# pca10056_sheet3_pin_map.net
KiCad netlist of a schematic drawn in Altium Designer
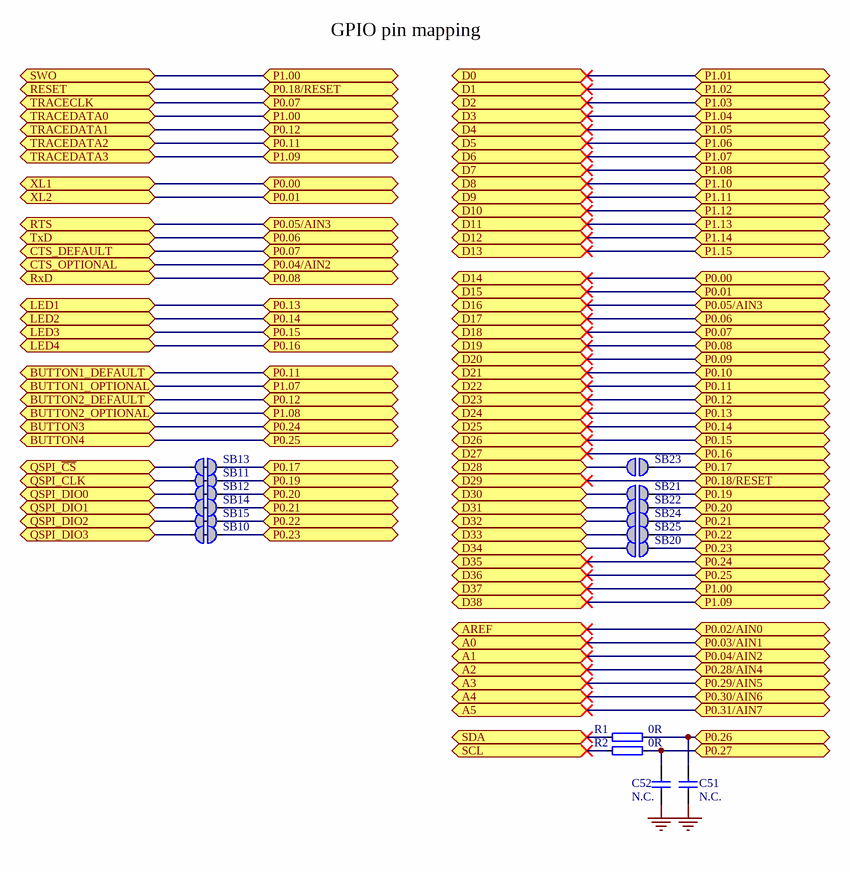
[diagram p0: pca10056_sheet3_pin_map.SchDoc]

(export (version "E")
  (design (tool "Eeschema 10.0.6"))
  (components
    (comp (ref "C51")
      (value "N.C.")
      (footprint "CAPC0603X03L_C")
      (description "Not mounted")
      (fields (field (name "PART NUMBER") "C0201-N.C.") (field (name "PUBLISHER") "Nordic Semiconductor"))
      (libsource (lib "Nordic Passive DB") (part "CAP"))
    )
    (comp (ref "C52")
      (value "N.C.")
      (footprint "CAPC0603X03L_C")
      (description "Not mounted")
      (fields (field (name "PART NUMBER") "C0201-N.C.") (field (name "PUBLISHER") "Nordic Semiconductor"))
      (libsource (lib "Nordic Passive DB") (part "CAP"))
    )
    (comp (ref "R1")
      (value "0R")
      (footprint "RESC0603X03L_C")
      (description "Resistor, ±5%, 0.05W")
      (fields (field (name "PART NUMBER") "R0201-0R") (field (name "PUBLISHER") "Nordic Semiconductor"))
      (libsource (lib "Nordic Passive DB") (part "RES_1"))
    )
    (comp (ref "R2")
      (value "0R")
      (footprint "RESC0603X03L_C")
      (description "Resistor, ±5%, 0.05W")
      (fields (field (name "PART NUMBER") "R0201-0R") (field (name "PUBLISHER") "Nordic Semiconductor"))
      (libsource (lib "Nordic Passive DB") (part "RES_1"))
    )
    (comp (ref "SB10")
      (value "Solderbridge")
      (footprint "Solderbridge_Shorted")
      (description "Shorted Solderbridge")
      (fields
        (field (name "PART NUMBER") "Solderbridge Shorted")
        (field (name "PUBLISHER") "Nordic Semiconductor")
      )
      (libsource (lib "Nordic Passive DB") (part "SOLDERBRIDGE_SHORTED"))
    )
    (comp (ref "SB11")
      (value "Solderbridge")
      (footprint "Solderbridge_Shorted")
      (description "Shorted Solderbridge")
      (fields
        (field (name "PART NUMBER") "Solderbridge Shorted")
        (field (name "PUBLISHER") "Nordic Semiconductor")
      )
      (libsource (lib "Nordic Passive DB") (part "SOLDERBRIDGE_SHORTED"))
    )
    (comp (ref "SB12")
      (value "Solderbridge")
      (footprint "Solderbridge_Shorted")
      (description "Shorted Solderbridge")
      (fields
        (field (name "PART NUMBER") "Solderbridge Shorted")
        (field (name "PUBLISHER") "Nordic Semiconductor")
      )
      (libsource (lib "Nordic Passive DB") (part "SOLDERBRIDGE_SHORTED"))
    )
    (comp (ref "SB13")
      (value "Solderbridge")
      (footprint "Solderbridge_Shorted")
      (description "Shorted Solderbridge")
      (fields
        (field (name "PART NUMBER") "Solderbridge Shorted")
        (field (name "PUBLISHER") "Nordic Semiconductor")
      )
      (libsource (lib "Nordic Passive DB") (part "SOLDERBRIDGE_SHORTED"))
    )
    (comp (ref "SB14")
      (value "Solderbridge")
      (footprint "Solderbridge_Shorted")
      (description "Shorted Solderbridge")
      (fields
        (field (name "PART NUMBER") "Solderbridge Shorted")
        (field (name "PUBLISHER") "Nordic Semiconductor")
      )
      (libsource (lib "Nordic Passive DB") (part "SOLDERBRIDGE_SHORTED"))
    )
    (comp (ref "SB15")
      (value "Solderbridge")
      (footprint "Solderbridge_Shorted")
      (description "Shorted Solderbridge")
      (fields
        (field (name "PART NUMBER") "Solderbridge Shorted")
        (field (name "PUBLISHER") "Nordic Semiconductor")
      )
      (libsource (lib "Nordic Passive DB") (part "SOLDERBRIDGE_SHORTED"))
    )
    (comp (ref "SB20")
      (value "Solderbridge")
      (footprint "Solderbridge")
      (fields (field (name "PUBLISHER") "Nordic Semiconductor"))
      (libsource (lib "Nordic Passive DB") (part "SOLDERBRIDGE"))
    )
    (comp (ref "SB21")
      (value "Solderbridge")
      (footprint "Solderbridge")
      (fields (field (name "PUBLISHER") "Nordic Semiconductor"))
      (libsource (lib "Nordic Passive DB") (part "SOLDERBRIDGE"))
    )
    (comp (ref "SB22")
      (value "Solderbridge")
      (footprint "Solderbridge")
      (fields (field (name "PUBLISHER") "Nordic Semiconductor"))
      (libsource (lib "Nordic Passive DB") (part "SOLDERBRIDGE"))
    )
    (comp (ref "SB23")
      (value "Solderbridge")
      (footprint "Solderbridge")
      (fields (field (name "PUBLISHER") "Nordic Semiconductor"))
      (libsource (lib "Nordic Passive DB") (part "SOLDERBRIDGE"))
    )
    (comp (ref "SB24")
      (value "Solderbridge")
      (footprint "Solderbridge")
      (fields (field (name "PUBLISHER") "Nordic Semiconductor"))
      (libsource (lib "Nordic Passive DB") (part "SOLDERBRIDGE"))
    )
    (comp (ref "SB25")
      (value "Solderbridge")
      (footprint "Solderbridge")
      (fields (field (name "PUBLISHER") "Nordic Semiconductor"))
      (libsource (lib "Nordic Passive DB") (part "SOLDERBRIDGE"))
    )
  )
  (nets
    (net (code "38") (name "/D28") (class "Default")
      (node (ref "SB23") (pin "2") (pinfunction "1_2") (pintype "passive"))
    )
    (net (code "40") (name "/D30") (class "Default")
      (node (ref "SB21") (pin "2") (pinfunction "1_2") (pintype "passive"))
    )
    (net (code "41") (name "/D31") (class "Default")
      (node (ref "SB22") (pin "2") (pinfunction "1_2") (pintype "passive"))
    )
    (net (code "42") (name "/D32") (class "Default")
      (node (ref "SB24") (pin "2") (pinfunction "1_2") (pintype "passive"))
    )
    (net (code "43") (name "/D33") (class "Default")
      (node (ref "SB25") (pin "2") (pinfunction "1_2") (pintype "passive"))
    )
    (net (code "44") (name "/D34") (class "Default")
      (node (ref "SB20") (pin "2") (pinfunction "1_2") (pintype "passive"))
    )
    (net (code "47") (name "/P0.17") (class "Default")
      (node (ref "SB13") (pin "1") (pinfunction "0_1") (pintype "passive"))
      (node (ref "SB23") (pin "1") (pinfunction "0_1") (pintype "passive"))
    )
    (net (code "48") (name "/P0.19") (class "Default")
      (node (ref "SB11") (pin "1") (pinfunction "0_1") (pintype "passive"))
      (node (ref "SB21") (pin "1") (pinfunction "0_1") (pintype "passive"))
    )
    (net (code "49") (name "/P0.20") (class "Default")
      (node (ref "SB12") (pin "1") (pinfunction "0_1") (pintype "passive"))
      (node (ref "SB22") (pin "1") (pinfunction "0_1") (pintype "passive"))
    )
    (net (code "50") (name "/P0.21") (class "Default")
      (node (ref "SB14") (pin "1") (pinfunction "0_1") (pintype "passive"))
      (node (ref "SB24") (pin "1") (pinfunction "0_1") (pintype "passive"))
    )
    (net (code "51") (name "/P0.22") (class "Default")
      (node (ref "SB15") (pin "1") (pinfunction "0_1") (pintype "passive"))
      (node (ref "SB25") (pin "1") (pinfunction "0_1") (pintype "passive"))
    )
    (net (code "52") (name "/P0.23") (class "Default")
      (node (ref "SB10") (pin "1") (pinfunction "0_1") (pintype "passive"))
      (node (ref "SB20") (pin "1") (pinfunction "0_1") (pintype "passive"))
    )
    (net (code "53") (name "/P0.26") (class "Default")
      (node (ref "C51") (pin "2") (pinfunction "2_2") (pintype "passive"))
      (node (ref "R1") (pin "2") (pinfunction "2_2") (pintype "passive"))
    )
    (net (code "54") (name "/P0.27") (class "Default")
      (node (ref "C52") (pin "1") (pinfunction "1_1") (pintype "passive"))
      (node (ref "R2") (pin "2") (pinfunction "2_2") (pintype "passive"))
    )
    (net (code "55") (name "/QSPI_CLK") (class "Default")
      (node (ref "SB11") (pin "2") (pinfunction "1_2") (pintype "passive"))
    )
    (net (code "56") (name "/QSPI_DIO0") (class "Default")
      (node (ref "SB12") (pin "2") (pinfunction "1_2") (pintype "passive"))
    )
    (net (code "57") (name "/QSPI_DIO1") (class "Default")
      (node (ref "SB14") (pin "2") (pinfunction "1_2") (pintype "passive"))
    )
    (net (code "58") (name "/QSPI_DIO2") (class "Default")
      (node (ref "SB15") (pin "2") (pinfunction "1_2") (pintype "passive"))
    )
    (net (code "59") (name "/QSPI_DIO3") (class "Default")
      (node (ref "SB10") (pin "2") (pinfunction "1_2") (pintype "passive"))
    )
    (net (code "60") (name "/QSPI_~{CS}") (class "Default")
      (node (ref "SB13") (pin "2") (pinfunction "1_2") (pintype "passive"))
    )
    (net (code "61") (name "/SCL") (class "Default")
      (node (ref "R2") (pin "1") (pinfunction "1_1") (pintype "passive+no_connect"))
    )
    (net (code "62") (name "/SDA") (class "Default")
      (node (ref "R1") (pin "1") (pinfunction "1_1") (pintype "passive+no_connect"))
    )
    (net (code "63") (name "GND") (class "Default")
      (node (ref "C51") (pin "1") (pinfunction "1_1") (pintype "passive"))
      (node (ref "C52") (pin "2") (pinfunction "2_2") (pintype "passive"))
    )
  )
)
